# OPAmp_Supply.net
KiCad netlist of a schematic drawn in Altium Designer
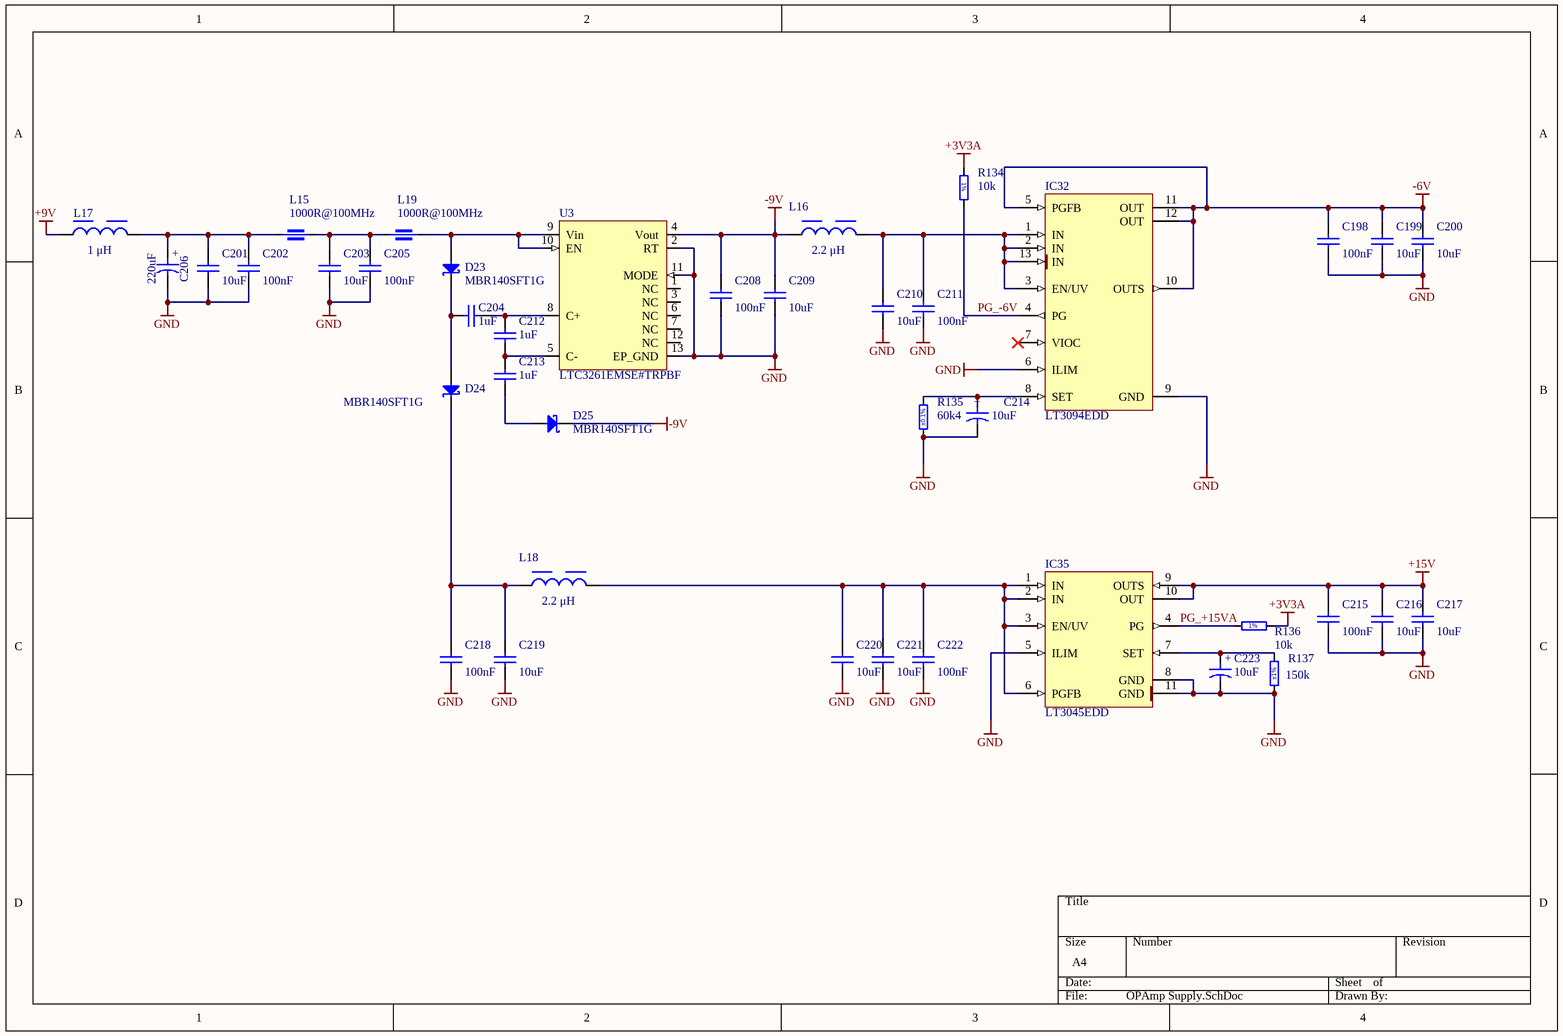
[diagram p0: OPAmp Supply.SchDoc]

(export (version "E")
  (design (tool "Eeschema 10.0.6"))
  (components
    (comp (ref "C198")
      (value "100nF")
      (footprint "CAPC1005X55N")
      (description "Non-polarised capacitor")
      (fields
        (field (name "PART NUMBER") "CC0402_100NF_16V_10%_X5R")
        (field (name "VOLTAGE") "16V")
        (field (name "AUTHOR") "CERN DEM JLC")
      )
      (libsource (lib "Capacitors") (part "Capacitor - non polarized"))
    )
    (comp (ref "C199")
      (value "10uF")
      (footprint "CAPC2012X145N")
      (description "Non-polarised capacitor")
      (fields
        (field (name "PART NUMBER") "CC0805_10UF_25V_10%_X7R")
        (field (name "VOLTAGE") "25V")
        (field (name "AUTHOR") "CERN DEM HF")
      )
      (libsource (lib "Capacitors") (part "Capacitor - non polarized"))
    )
    (comp (ref "C200")
      (value "10uF")
      (footprint "CAPC2012X145N")
      (description "Non-polarised capacitor")
      (fields
        (field (name "PART NUMBER") "CC0805_10UF_25V_10%_X7R")
        (field (name "VOLTAGE") "25V")
        (field (name "AUTHOR") "CERN DEM HF")
      )
      (libsource (lib "Capacitors") (part "Capacitor - non polarized"))
    )
    (comp (ref "C201")
      (value "10uF")
      (footprint "CAPC2012X145N")
      (description "Non-polarised capacitor")
      (fields
        (field (name "PART NUMBER") "CC0805_10UF_25V_10%_X7R")
        (field (name "VOLTAGE") "25V")
        (field (name "AUTHOR") "CERN DEM HF")
      )
      (libsource (lib "Capacitors") (part "Capacitor - non polarized"))
    )
    (comp (ref "C202")
      (value "100nF")
      (footprint "CAPC1005X55N")
      (description "Non-polarised capacitor")
      (fields
        (field (name "PART NUMBER") "CC0402_100NF_16V_10%_X5R")
        (field (name "VOLTAGE") "16V")
        (field (name "AUTHOR") "CERN DEM JLC")
      )
      (libsource (lib "Capacitors") (part "Capacitor - non polarized"))
    )
    (comp (ref "C203")
      (value "10uF")
      (footprint "CAPC2012X145N")
      (description "Non-polarised capacitor")
      (fields
        (field (name "PART NUMBER") "CC0805_10UF_25V_10%_X7R")
        (field (name "VOLTAGE") "25V")
        (field (name "AUTHOR") "CERN DEM HF")
      )
      (libsource (lib "Capacitors") (part "Capacitor - non polarized"))
    )
    (comp (ref "C204")
      (value "1uF")
      (footprint "CAPC1608X87N")
      (description "Non-polarised capacitor")
      (fields
        (field (name "PART NUMBER") "CC0603_1UF_25V_10%_X7R")
        (field (name "VOLTAGE") "25V")
        (field (name "AUTHOR") "CERN DEM JLC")
      )
      (libsource (lib "Capacitors") (part "Capacitor - non polarized"))
    )
    (comp (ref "C205")
      (value "100nF")
      (footprint "CAPC1005X55N")
      (description "Non-polarised capacitor")
      (fields
        (field (name "PART NUMBER") "CC0402_100NF_16V_10%_X5R")
        (field (name "VOLTAGE") "16V")
        (field (name "AUTHOR") "CERN DEM JLC")
      )
      (libsource (lib "Capacitors") (part "Capacitor - non polarized"))
    )
    (comp (ref "C206")
      (value "220uF")
      (footprint "CAPMP7343X430N")
      (description "Polarised capacitor")
      (fields
        (field (name "PART NUMBER") "CTE7343-43_220UF_16V_10%")
        (field (name "VOLTAGE") "16V")
        (field (name "AUTHOR") "CERN DEM JLC")
      )
      (libsource (lib "Capacitors") (part "Capacitor - polarized"))
    )
    (comp (ref "C208")
      (value "100nF")
      (footprint "CAPC1005X55N")
      (description "Non-polarised capacitor")
      (fields
        (field (name "PART NUMBER") "CC0402_100NF_16V_10%_X5R")
        (field (name "VOLTAGE") "16V")
        (field (name "AUTHOR") "CERN DEM JLC")
      )
      (libsource (lib "Capacitors") (part "Capacitor - non polarized"))
    )
    (comp (ref "C209")
      (value "10uF")
      (footprint "CAPC2012X145N")
      (description "Non-polarised capacitor")
      (fields
        (field (name "PART NUMBER") "CC0805_10UF_25V_10%_X7R")
        (field (name "VOLTAGE") "25V")
        (field (name "AUTHOR") "CERN DEM HF")
      )
      (libsource (lib "Capacitors") (part "Capacitor - non polarized"))
    )
    (comp (ref "C210")
      (value "10uF")
      (footprint "CAPC2012X145N")
      (description "Non-polarised capacitor")
      (fields
        (field (name "PART NUMBER") "CC0805_10UF_25V_10%_X7R")
        (field (name "VOLTAGE") "25V")
        (field (name "AUTHOR") "CERN DEM HF")
      )
      (libsource (lib "Capacitors") (part "Capacitor - non polarized"))
    )
    (comp (ref "C211")
      (value "100nF")
      (footprint "CAPC1005X55N")
      (description "Non-polarised capacitor")
      (fields
        (field (name "PART NUMBER") "CC0402_100NF_16V_10%_X5R")
        (field (name "VOLTAGE") "16V")
        (field (name "AUTHOR") "CERN DEM JLC")
      )
      (libsource (lib "Capacitors") (part "Capacitor - non polarized"))
    )
    (comp (ref "C212")
      (value "1uF")
      (footprint "CAPC1608X87N")
      (description "Non-polarised capacitor")
      (fields
        (field (name "PART NUMBER") "CC0603_1UF_25V_10%_X7R")
        (field (name "VOLTAGE") "25V")
        (field (name "AUTHOR") "CERN DEM JLC")
      )
      (libsource (lib "Capacitors") (part "Capacitor - non polarized"))
    )
    (comp (ref "C213")
      (value "1uF")
      (footprint "CAPC1608X87N")
      (description "Non-polarised capacitor")
      (fields
        (field (name "PART NUMBER") "CC0603_1UF_25V_10%_X7R")
        (field (name "VOLTAGE") "25V")
        (field (name "AUTHOR") "CERN DEM JLC")
      )
      (libsource (lib "Capacitors") (part "Capacitor - non polarized"))
    )
    (comp (ref "C214")
      (value "10uF")
      (footprint "CAPMP6032X280N")
      (description "Polarised capacitor")
      (fields
        (field (name "PART NUMBER") "CTE6032-28_10UF_25V_10%_LESR0500")
        (field (name "VOLTAGE") "25V")
        (field (name "AUTHOR") "CERN DEM JLC")
      )
      (libsource (lib "") (part "Capacitor - polarized_1"))
    )
    (comp (ref "C215")
      (value "100nF")
      (footprint "CAPC1005X55N")
      (description "Non-polarised capacitor")
      (fields
        (field (name "PART NUMBER") "CC0402_100NF_16V_10%_X5R")
        (field (name "VOLTAGE") "16V")
        (field (name "AUTHOR") "CERN DEM JLC")
      )
      (libsource (lib "Capacitors") (part "Capacitor - non polarized"))
    )
    (comp (ref "C216")
      (value "10uF")
      (footprint "CAPC2012X145N")
      (description "Non-polarised capacitor")
      (fields
        (field (name "PART NUMBER") "CC0805_10UF_25V_10%_X7R")
        (field (name "VOLTAGE") "25V")
        (field (name "AUTHOR") "CERN DEM HF")
      )
      (libsource (lib "Capacitors") (part "Capacitor - non polarized"))
    )
    (comp (ref "C217")
      (value "10uF")
      (footprint "CAPC2012X145N")
      (description "Non-polarised capacitor")
      (fields
        (field (name "PART NUMBER") "CC0805_10UF_25V_10%_X7R")
        (field (name "VOLTAGE") "25V")
        (field (name "AUTHOR") "CERN DEM HF")
      )
      (libsource (lib "Capacitors") (part "Capacitor - non polarized"))
    )
    (comp (ref "C218")
      (value "100nF")
      (footprint "CAPC1005X55N")
      (description "Non-polarised capacitor")
      (fields
        (field (name "PART NUMBER") "CC0402_100NF_16V_10%_X5R")
        (field (name "VOLTAGE") "16V")
        (field (name "AUTHOR") "CERN DEM JLC")
      )
      (libsource (lib "Capacitors") (part "Capacitor - non polarized"))
    )
    (comp (ref "C219")
      (value "10uF")
      (footprint "CAPC2012X145N")
      (description "Non-polarised capacitor")
      (fields
        (field (name "PART NUMBER") "CC0805_10UF_25V_10%_X7R")
        (field (name "VOLTAGE") "25V")
        (field (name "AUTHOR") "CERN DEM HF")
      )
      (libsource (lib "Capacitors") (part "Capacitor - non polarized"))
    )
    (comp (ref "C220")
      (value "10uF")
      (footprint "CAPC2012X145N")
      (description "Non-polarised capacitor")
      (fields
        (field (name "PART NUMBER") "CC0805_10UF_25V_10%_X7R")
        (field (name "VOLTAGE") "25V")
        (field (name "AUTHOR") "CERN DEM HF")
      )
      (libsource (lib "Capacitors") (part "Capacitor - non polarized"))
    )
    (comp (ref "C221")
      (value "10uF")
      (footprint "CAPC2012X145N")
      (description "Non-polarised capacitor")
      (fields
        (field (name "PART NUMBER") "CC0805_10UF_25V_10%_X7R")
        (field (name "VOLTAGE") "25V")
        (field (name "AUTHOR") "CERN DEM HF")
      )
      (libsource (lib "Capacitors") (part "Capacitor - non polarized"))
    )
    (comp (ref "C222")
      (value "100nF")
      (footprint "CAPC1005X55N")
      (description "Non-polarised capacitor")
      (fields
        (field (name "PART NUMBER") "CC0402_100NF_16V_10%_X5R")
        (field (name "VOLTAGE") "16V")
        (field (name "AUTHOR") "CERN DEM JLC")
      )
      (libsource (lib "Capacitors") (part "Capacitor - non polarized"))
    )
    (comp (ref "C223")
      (value "10uF")
      (footprint "CAPMP6032X280N")
      (description "Polarised capacitor")
      (fields
        (field (name "PART NUMBER") "CTE6032-28_10UF_25V_10%_LESR0500")
        (field (name "VOLTAGE") "25V")
        (field (name "AUTHOR") "CERN DEM JLC")
      )
      (libsource (lib "Capacitors") (part "Capacitor - polarized"))
    )
    (comp (ref "D23")
      (value "MBR140SFT1G")
      (footprint "SOD-123FL")
      (description "Schottky Diode")
      (fields
        (field (name "VOLTAGE") "40V")
        (field (name "POWER") "1A")
        (field (name "AUTHOR") "CERN DEM JLC")
      )
      (libsource (lib "ICs And Semiconductors") (part "Diode Schottky"))
    )
    (comp (ref "D24")
      (value "MBR140SFT1G")
      (footprint "SOD-123FL")
      (description "Schottky Diode")
      (fields
        (field (name "VOLTAGE") "40V")
        (field (name "POWER") "1A")
        (field (name "AUTHOR") "CERN DEM JLC")
      )
      (libsource (lib "ICs And Semiconductors") (part "Diode Schottky"))
    )
    (comp (ref "D25")
      (value "MBR140SFT1G")
      (footprint "SOD-123FL")
      (description "Schottky Diode")
      (fields
        (field (name "VOLTAGE") "40V")
        (field (name "POWER") "1A")
        (field (name "AUTHOR") "CERN DEM JLC")
      )
      (libsource (lib "ICs And Semiconductors") (part "Diode Schottky"))
    )
    (comp (ref "IC32")
      (value "LT3094EDD")
      (footprint "SON45P300X300X80-13N-R175X248")
      (description "-20V, 500mA, Ultralow Noise, Ultrahigh PSRR Negative Linear Regulator")
      (fields
        (field (name "PART NUMBER") "LT3094EDD#PBF")
        (field (name "MANUFACTURER") "LINEAR TECHNOLOGY")
        (field (name "AUTHOR") "CERN DEM JLC")
      )
      (libsource (lib "ICs And Semiconductors") (part "LT3094"))
    )
    (comp (ref "IC35")
      (value "LT3045EDD")
      (footprint "SON50P300X300X80-11N-R175X248")
      (description "20V, 500mA, Ultralow Noise, Ultrahigh PSRR Linear Regulator")
      (fields
        (field (name "PART NUMBER") "LT3045EDD#PBF")
        (field (name "MANUFACTURER") "LINEAR TECHNOLOGY")
        (field (name "AUTHOR") "CERN DEM JLC")
      )
      (libsource (lib "ICs And Semiconductors") (part "LT3045EDD"))
    )
    (comp (ref "L15")
      (value "1000R@100MHz")
      (footprint "INDC1608X95N")
      (fields
        (field (name "PART NUMBER") "IND0603_MURATA_BLM18KG102SN1")
        (field (name "POWER") "1A")
        (field (name "TOLERANCE") "±25%")
        (field (name "AUTHOR") "CERN DEM HF")
      )
      (libsource (lib "Inductors & Transformers") (part "Ferrite Bead"))
    )
    (comp (ref "L16")
      (value "2.2 μH")
      (footprint "WE-MAPI_1610")
      (description "WE-MAPI SMT Power Inductor, size 1610, 2.2 μH, 1.25 A, 337 mΩ")
      (fields
        (field (name "MANUFACTURER PART NUMBER") "74438313022")
        (field (name "MANUFACTURER") "Wurth Elektronik")
      )
      (libsource (lib "WE-MAPI (rev25a)") (part "74438313022"))
    )
    (comp (ref "L17")
      (value "1 μH")
      (footprint "WE-MAPI_2510")
      (description "WE-MAPI SMT Power Inductor, size 2510, 1 μH, 3.55 A, 63 mΩ")
      (fields
        (field (name "MANUFACTURER PART NUMBER") "74438323010")
        (field (name "MANUFACTURER") "Wurth Elektronik")
      )
      (libsource (lib "WE-MAPI (rev25a)") (part "74438323010"))
    )
    (comp (ref "L18")
      (value "2.2 μH")
      (footprint "WE-MAPI_1610")
      (description "WE-MAPI SMT Power Inductor, size 1610, 2.2 μH, 1.25 A, 337 mΩ")
      (fields
        (field (name "MANUFACTURER PART NUMBER") "74438313022")
        (field (name "MANUFACTURER") "Wurth Elektronik")
      )
      (libsource (lib "WE-MAPI (rev25a)") (part "74438313022"))
    )
    (comp (ref "L19")
      (value "1000R@100MHz")
      (footprint "INDC1608X95N")
      (fields
        (field (name "PART NUMBER") "IND0603_MURATA_BLM18KG102SN1")
        (field (name "POWER") "1A")
        (field (name "TOLERANCE") "±25%")
        (field (name "AUTHOR") "CERN DEM HF")
      )
      (libsource (lib "Inductors & Transformers") (part "Ferrite Bead"))
    )
    (comp (ref "R134")
      (value "10k")
      (footprint "RESC1005X40N")
      (description "Resistor - 1%")
      (fields
        (field (name "PART NUMBER") "R0402_10K_1%_0.0625W_100PPM")
        (field (name "POWER") "0.0625W")
        (field (name "AUTHOR") "CERN DEM JLC")
      )
      (libsource (lib "Resistors") (part "Resistor - 1%"))
    )
    (comp (ref "R135")
      (value "60k4")
      (footprint "RESC1608X55N")
      (description "Resistor - 0.1%")
      (fields
        (field (name "TOLERANCE") "±0.1%")
        (field (name "PART NUMBER") "R0603_60K4_0.1%_0.063W_10PPM")
        (field (name "POWER") "0.063W")
        (field (name "AUTHOR") "CERN DEM JLC")
      )
      (libsource (lib "Resistors") (part "Resistor - 0.1%"))
    )
    (comp (ref "R136")
      (value "10k")
      (footprint "RESC1005X40N")
      (description "Resistor - 1%")
      (fields
        (field (name "PART NUMBER") "R0402_10K_1%_0.0625W_100PPM")
        (field (name "POWER") "0.0625W")
        (field (name "AUTHOR") "CERN DEM JLC")
      )
      (libsource (lib "Resistors") (part "Resistor - 1%"))
    )
    (comp (ref "R137")
      (value "150k")
      (footprint "RESC1608X55N")
      (description "Resistor - 1%")
      (fields
        (field (name "TOLERANCE") "±1%")
        (field (name "PART NUMBER") "R0603_150K_1%_0.1W_100PPM")
        (field (name "POWER") "0.1W")
        (field (name "AUTHOR") "CERN DEM JLC")
      )
      (libsource (lib "") (part "Resistor - 1%_1"))
    )
    (comp (ref "U3")
      (value "LTC3261EMSE#TRPBF")
      (footprint "TSSOP-12")
      (libsource (lib "Component Library 3.2") (part "LTC3261EMSE#TRPBF"))
    )
  )
  (nets
    (net (code "1") (name "+3V3A") (class "Default")
      (node (ref "R134") (pin "2") (pinfunction "2_2") (pintype "passive"))
      (node (ref "R136") (pin "2") (pinfunction "2_2") (pintype "passive"))
    )
    (net (code "2") (name "+9V") (class "Default")
      (node (ref "L17") (pin "1") (pinfunction "1_1") (pintype "passive"))
    )
    (net (code "3") (name "+15V") (class "Default")
      (node (ref "C215") (pin "1") (pinfunction "1_1") (pintype "passive"))
      (node (ref "C216") (pin "2") (pinfunction "2_2") (pintype "passive"))
      (node (ref "C217") (pin "2") (pinfunction "2_2") (pintype "passive"))
      (node (ref "IC35") (pin "10") (pinfunction "OUT_10") (pintype "power_in"))
      (node (ref "IC35") (pin "9") (pinfunction "OUTS_9") (pintype "input"))
    )
    (net (code "4") (name "-6V") (class "Default")
      (node (ref "C198") (pin "1") (pinfunction "1_1") (pintype "passive"))
      (node (ref "C199") (pin "2") (pinfunction "2_2") (pintype "passive"))
      (node (ref "C200") (pin "2") (pinfunction "2_2") (pintype "passive"))
      (node (ref "IC32") (pin "10") (pinfunction "OUTS_10") (pintype "output"))
      (node (ref "IC32") (pin "11") (pinfunction "OUT_11") (pintype "power_in"))
      (node (ref "IC32") (pin "12") (pinfunction "OUT_12") (pintype "power_in"))
      (node (ref "IC32") (pin "5") (pinfunction "PGFB_5") (pintype "input"))
    )
    (net (code "5") (name "-9V") (class "Default")
      (node (ref "C208") (pin "1") (pinfunction "1_1") (pintype "passive"))
      (node (ref "C209") (pin "2") (pinfunction "2_2") (pintype "passive"))
      (node (ref "D25") (pin "1") (pinfunction "C_1") (pintype "passive"))
      (node (ref "L16") (pin "1") (pinfunction "1_1") (pintype "passive"))
      (node (ref "U3") (pin "4") (pinfunction "Vout_4") (pintype "power_in"))
    )
    (net (code "6") (name "/PG_+15VA") (class "Default")
      (node (ref "IC35") (pin "4") (pinfunction "PG_4") (pintype "output"))
      (node (ref "R136") (pin "1") (pinfunction "1_1") (pintype "passive"))
    )
    (net (code "7") (name "/PG_-6V") (class "Default")
      (node (ref "IC32") (pin "4") (pinfunction "PG_4") (pintype "output"))
      (node (ref "R134") (pin "1") (pinfunction "1_1") (pintype "passive"))
    )
    (net (code "8") (name "GND") (class "Default")
      (node (ref "C198") (pin "2") (pinfunction "2_2") (pintype "passive"))
      (node (ref "C199") (pin "1") (pinfunction "1_1") (pintype "passive"))
      (node (ref "C200") (pin "1") (pinfunction "1_1") (pintype "passive"))
      (node (ref "C201") (pin "1") (pinfunction "1_1") (pintype "passive"))
      (node (ref "C202") (pin "2") (pinfunction "2_2") (pintype "passive"))
      (node (ref "C203") (pin "1") (pinfunction "1_1") (pintype "passive"))
      (node (ref "C205") (pin "2") (pinfunction "2_2") (pintype "passive"))
      (node (ref "C206") (pin "2") (pinfunction "2_2") (pintype "passive"))
      (node (ref "C208") (pin "2") (pinfunction "2_2") (pintype "passive"))
      (node (ref "C209") (pin "1") (pinfunction "1_1") (pintype "passive"))
      (node (ref "C210") (pin "1") (pinfunction "1_1") (pintype "passive"))
      (node (ref "C211") (pin "2") (pinfunction "2_2") (pintype "passive"))
      (node (ref "C214") (pin "2") (pinfunction "2_2") (pintype "passive"))
      (node (ref "C215") (pin "2") (pinfunction "2_2") (pintype "passive"))
      (node (ref "C216") (pin "1") (pinfunction "1_1") (pintype "passive"))
      (node (ref "C217") (pin "1") (pinfunction "1_1") (pintype "passive"))
      (node (ref "C218") (pin "2") (pinfunction "2_2") (pintype "passive"))
      (node (ref "C219") (pin "1") (pinfunction "1_1") (pintype "passive"))
      (node (ref "C220") (pin "1") (pinfunction "1_1") (pintype "passive"))
      (node (ref "C221") (pin "1") (pinfunction "1_1") (pintype "passive"))
      (node (ref "C222") (pin "2") (pinfunction "2_2") (pintype "passive"))
      (node (ref "C223") (pin "2") (pinfunction "2_2") (pintype "passive"))
      (node (ref "IC32") (pin "6") (pinfunction "ILIM_6") (pintype "input"))
      (node (ref "IC32") (pin "9") (pinfunction "GND_9") (pintype "power_in"))
      (node (ref "IC35") (pin "11") (pinfunction "GND_11") (pintype "power_in"))
      (node (ref "IC35") (pin "5") (pinfunction "ILIM_5") (pintype "input"))
      (node (ref "IC35") (pin "8") (pinfunction "GND_8") (pintype "power_in"))
      (node (ref "R135") (pin "1") (pinfunction "1_1") (pintype "passive"))
      (node (ref "R137") (pin "1") (pinfunction "1_1") (pintype "passive"))
      (node (ref "U3") (pin "11") (pinfunction "MODE_11") (pintype "input"))
      (node (ref "U3") (pin "13") (pinfunction "EP_GND_13") (pintype "passive"))
      (node (ref "U3") (pin "2") (pinfunction "RT_2") (pintype "passive"))
    )
    (net (code "9") (name "Net-(C201-Pad2)") (class "Default")
      (node (ref "C201") (pin "2") (pinfunction "2_2") (pintype "passive"))
      (node (ref "C202") (pin "1") (pinfunction "1_1") (pintype "passive"))
      (node (ref "C206") (pin "1") (pinfunction "1_1") (pintype "passive"))
      (node (ref "L15") (pin "1") (pinfunction "1_1") (pintype "passive"))
      (node (ref "L17") (pin "2") (pinfunction "2_2") (pintype "passive"))
    )
    (net (code "10") (name "Net-(C203-Pad2)") (class "Default")
      (node (ref "C203") (pin "2") (pinfunction "2_2") (pintype "passive"))
      (node (ref "C205") (pin "1") (pinfunction "1_1") (pintype "passive"))
      (node (ref "L15") (pin "2") (pinfunction "2_2") (pintype "passive"))
      (node (ref "L19") (pin "1") (pinfunction "1_1") (pintype "passive"))
    )
    (net (code "11") (name "Net-(D23-A)") (class "Default")
      (node (ref "D23") (pin "2") (pinfunction "A_2") (pintype "passive"))
      (node (ref "L19") (pin "2") (pinfunction "2_2") (pintype "passive"))
      (node (ref "U3") (pin "10") (pinfunction "EN_10") (pintype "input"))
      (node (ref "U3") (pin "9") (pinfunction "Vin_9") (pintype "power_in"))
    )
    (net (code "12") (name "Net-(D23-C)") (class "Default")
      (node (ref "C204") (pin "2") (pinfunction "2_2") (pintype "passive"))
      (node (ref "D23") (pin "1") (pinfunction "C_1") (pintype "passive"))
      (node (ref "D24") (pin "2") (pinfunction "A_2") (pintype "passive"))
    )
    (net (code "13") (name "Net-(D24-C)") (class "Default")
      (node (ref "C218") (pin "1") (pinfunction "1_1") (pintype "passive"))
      (node (ref "C219") (pin "2") (pinfunction "2_2") (pintype "passive"))
      (node (ref "D24") (pin "1") (pinfunction "C_1") (pintype "passive"))
      (node (ref "L18") (pin "1") (pinfunction "1_1") (pintype "passive"))
    )
    (net (code "14") (name "Net-(D25-A)") (class "Default")
      (node (ref "C213") (pin "1") (pinfunction "1_1") (pintype "passive"))
      (node (ref "D25") (pin "2") (pinfunction "A_2") (pintype "passive"))
    )
    (net (code "15") (name "Net-(IC32-EN{slash}UV)") (class "Default")
      (node (ref "C210") (pin "2") (pinfunction "2_2") (pintype "passive"))
      (node (ref "C211") (pin "1") (pinfunction "1_1") (pintype "passive"))
      (node (ref "IC32") (pin "1") (pinfunction "IN_1") (pintype "input"))
      (node (ref "IC32") (pin "13") (pinfunction "IN_13") (pintype "input"))
      (node (ref "IC32") (pin "2") (pinfunction "IN_2") (pintype "input"))
      (node (ref "IC32") (pin "3") (pinfunction "EN/UV_3") (pintype "input"))
      (node (ref "L16") (pin "2") (pinfunction "2_2") (pintype "passive"))
    )
    (net (code "16") (name "Net-(IC32-SET)") (class "Default")
      (node (ref "C214") (pin "1") (pinfunction "1_1") (pintype "passive"))
      (node (ref "IC32") (pin "8") (pinfunction "SET_8") (pintype "input"))
      (node (ref "R135") (pin "2") (pinfunction "2_2") (pintype "passive"))
    )
    (net (code "17") (name "Net-(IC35-EN{slash}UV)") (class "Default")
      (node (ref "C220") (pin "2") (pinfunction "2_2") (pintype "passive"))
      (node (ref "C221") (pin "2") (pinfunction "2_2") (pintype "passive"))
      (node (ref "C222") (pin "1") (pinfunction "1_1") (pintype "passive"))
      (node (ref "IC35") (pin "1") (pinfunction "IN_1") (pintype "input"))
      (node (ref "IC35") (pin "2") (pinfunction "IN_2") (pintype "input"))
      (node (ref "IC35") (pin "3") (pinfunction "EN/UV_3") (pintype "input"))
      (node (ref "IC35") (pin "6") (pinfunction "PGFB_6") (pintype "input"))
      (node (ref "L18") (pin "2") (pinfunction "2_2") (pintype "passive"))
    )
    (net (code "18") (name "Net-(IC35-SET)") (class "Default")
      (node (ref "C223") (pin "1") (pinfunction "1_1") (pintype "passive"))
      (node (ref "IC35") (pin "7") (pinfunction "SET_7") (pintype "input"))
      (node (ref "R137") (pin "2") (pinfunction "2_2") (pintype "passive"))
    )
    (net (code "19") (name "Net-(U3-C+)") (class "Default")
      (node (ref "C204") (pin "1") (pinfunction "1_1") (pintype "passive"))
      (node (ref "C212") (pin "2") (pinfunction "2_2") (pintype "passive"))
      (node (ref "U3") (pin "8") (pinfunction "C+_8") (pintype "passive"))
    )
    (net (code "20") (name "Net-(U3-C-)") (class "Default")
      (node (ref "C212") (pin "1") (pinfunction "1_1") (pintype "passive"))
      (node (ref "C213") (pin "2") (pinfunction "2_2") (pintype "passive"))
      (node (ref "U3") (pin "5") (pinfunction "C-_5") (pintype "passive"))
    )
    (net (code "21") (name "unconnected-(IC32-VIOC-Pad7)") (class "Default")
      (node (ref "IC32") (pin "7") (pinfunction "VIOC_7") (pintype "input+no_connect"))
    )
    (net (code "22") (name "unconnected-(U3-NC-Pad1)") (class "Default")
      (node (ref "U3") (pin "1") (pinfunction "NC_1") (pintype "passive"))
    )
    (net (code "23") (name "unconnected-(U3-NC-Pad3)") (class "Default")
      (node (ref "U3") (pin "3") (pinfunction "NC_3") (pintype "passive"))
    )
    (net (code "24") (name "unconnected-(U3-NC-Pad6)") (class "Default")
      (node (ref "U3") (pin "6") (pinfunction "NC_6") (pintype "passive"))
    )
    (net (code "25") (name "unconnected-(U3-NC-Pad7)") (class "Default")
      (node (ref "U3") (pin "7") (pinfunction "NC_7") (pintype "passive"))
    )
    (net (code "26") (name "unconnected-(U3-NC-Pad12)") (class "Default")
      (node (ref "U3") (pin "12") (pinfunction "NC_12") (pintype "passive"))
    )
  )
)
